# working.net
KiCad netlist of a schematic drawn in EAGLE
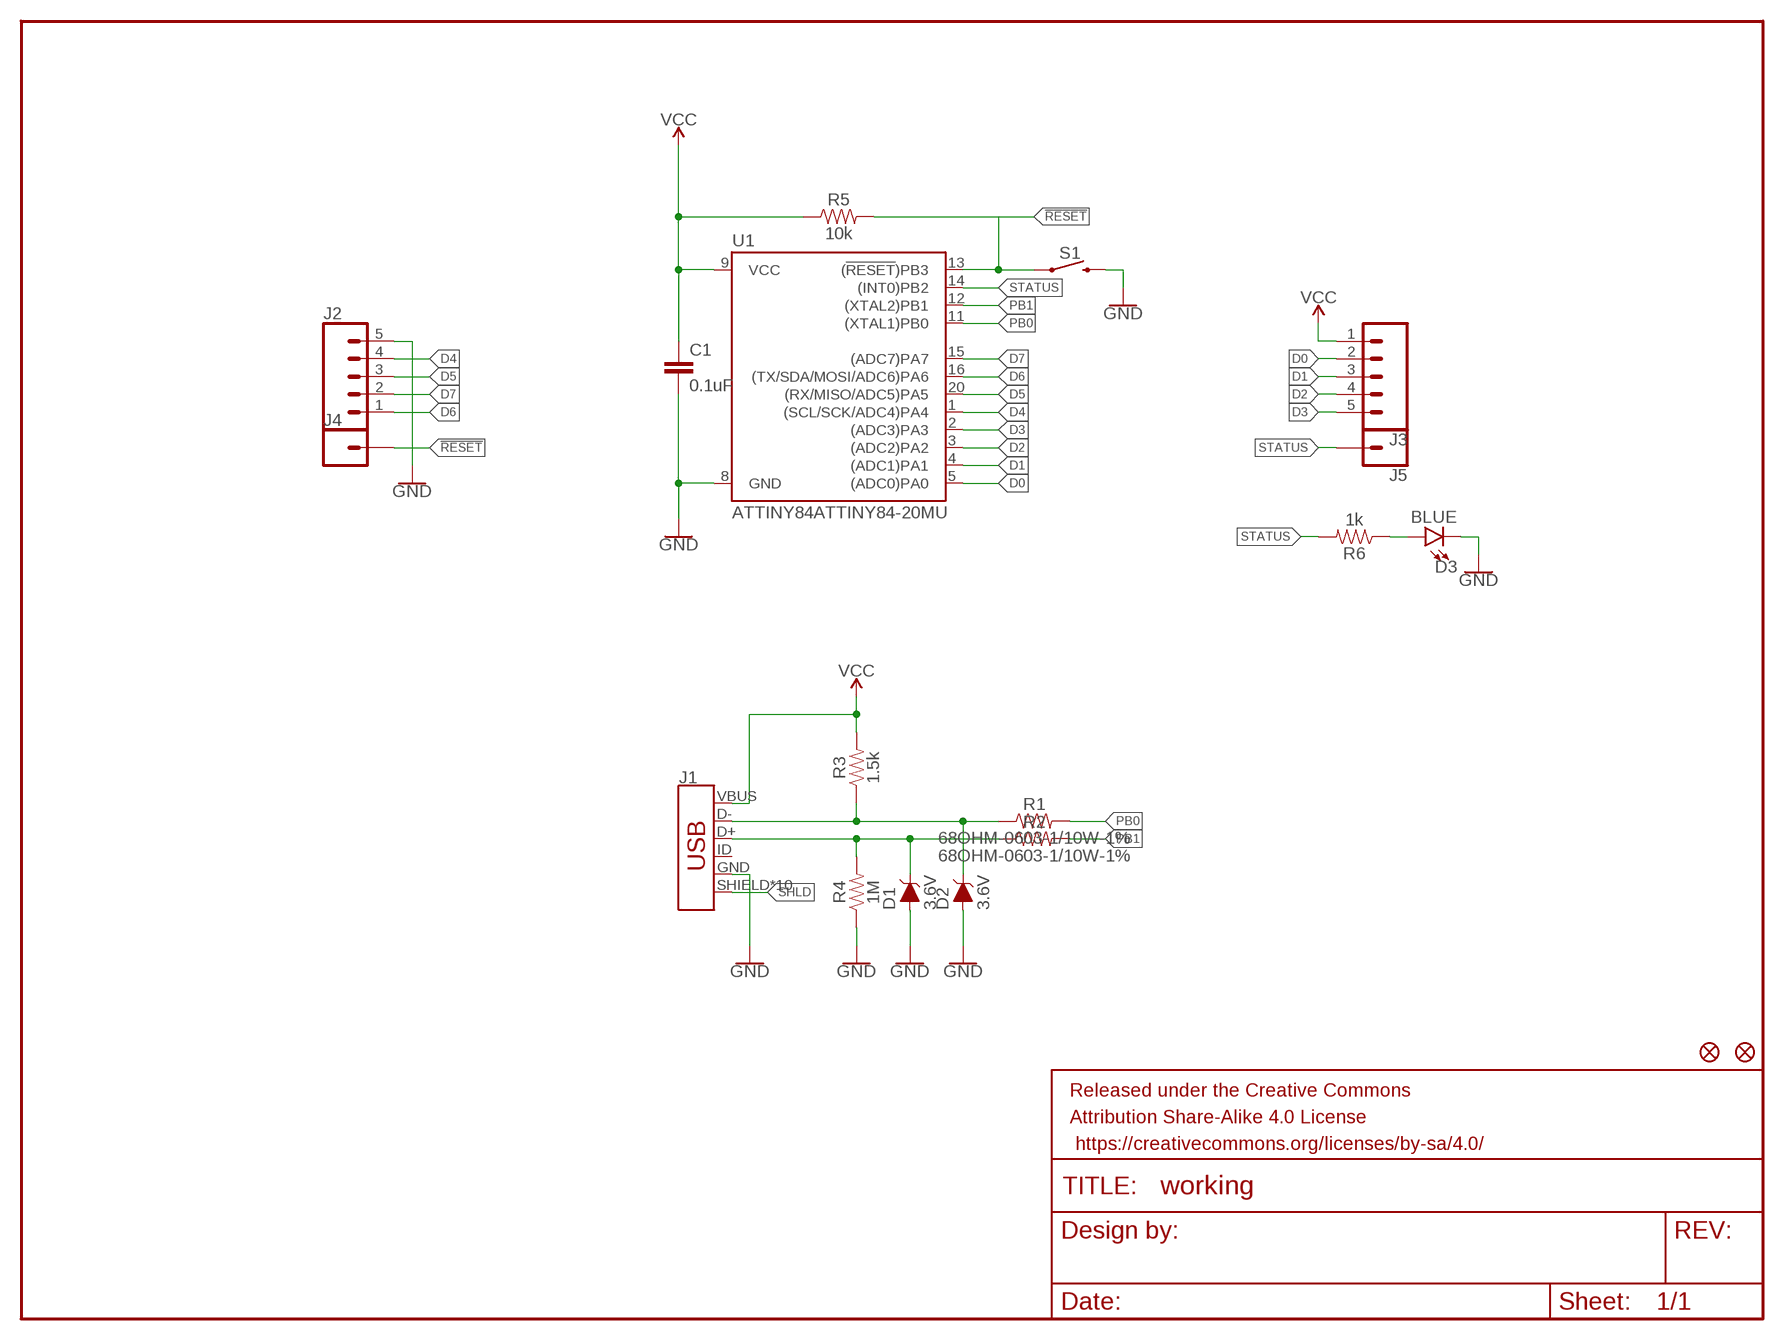
[diagram p0: schematic, sheet 1]

(export (version "E")
  (design (tool "Eeschema 10.0.6"))
  (components
    (comp (ref "C1")
      (value "0.1uF")
      (footprint "eagle-import:0603")
      (libsource (lib "eagle-import") (part "0.1UF-0603-25V-(+80/-20%)"))
    )
    (comp (ref "D1")
      (value "3.6V")
      (footprint "eagle-import:SOD-323")
      (libsource (lib "eagle-import") (part "DIODE-ZENER-BZT52C3V6S"))
    )
    (comp (ref "D2")
      (value "3.6V")
      (footprint "eagle-import:SOD-323")
      (libsource (lib "eagle-import") (part "DIODE-ZENER-BZT52C3V6S"))
    )
    (comp (ref "D3")
      (value "BLUE")
      (footprint "eagle-import:LED-0603")
      (libsource (lib "eagle-import") (part "LED-BLUE0603"))
    )
    (comp (ref "FD1")
      (value "FIDUCIALUFIDUCIAL")
      (footprint "eagle-import:FIDUCIAL-MICRO")
      (libsource (lib "eagle-import") (part "FIDUCIALUFIDUCIAL"))
    )
    (comp (ref "FD2")
      (value "FIDUCIALUFIDUCIAL")
      (footprint "eagle-import:FIDUCIAL-MICRO")
      (libsource (lib "eagle-import") (part "FIDUCIALUFIDUCIAL"))
    )
    (comp (ref "FRAME1")
      (value "FRAME-LETTER")
      (footprint "eagle-import:CREATIVE_COMMONS")
      (libsource (lib "eagle-import") (part "FRAME-LETTER"))
    )
    (comp (ref "J1")
      (value "USB_MICRO-B_HALF_PTH_MILL")
      (footprint "eagle-import:USB-MICROB-PTH-MILL")
      (libsource (lib "eagle-import") (part "USB_MICRO-B_HALF_PTH_MILL"))
    )
    (comp (ref "J2")
      (value "CONN_05NO_SILK")
      (footprint "eagle-import:1X05_NO_SILK")
      (libsource (lib "eagle-import") (part "CONN_05NO_SILK"))
    )
    (comp (ref "J3")
      (value "CONN_05NO_SILK")
      (footprint "eagle-import:1X05_NO_SILK")
      (libsource (lib "eagle-import") (part "CONN_05NO_SILK"))
    )
    (comp (ref "J4")
      (value "CONN_01PTH_NO_SILK_YES_STOP")
      (footprint "eagle-import:1X01_NO_SILK")
      (libsource (lib "eagle-import") (part "CONN_01PTH_NO_SILK_YES_STOP"))
    )
    (comp (ref "J5")
      (value "CONN_01PTH_NO_SILK_YES_STOP")
      (footprint "eagle-import:1X01_NO_SILK")
      (libsource (lib "eagle-import") (part "CONN_01PTH_NO_SILK_YES_STOP"))
    )
    (comp (ref "R1")
      (value "68OHM-0603-1/10W-1%")
      (footprint "eagle-import:0603")
      (libsource (lib "eagle-import") (part "68OHM-0603-1/10W-1%"))
    )
    (comp (ref "R2")
      (value "68OHM-0603-1/10W-1%")
      (footprint "eagle-import:0603")
      (libsource (lib "eagle-import") (part "68OHM-0603-1/10W-1%"))
    )
    (comp (ref "R3")
      (value "1.5k")
      (footprint "eagle-import:0603")
      (libsource (lib "eagle-import") (part "1.5KOHM-0603-1/10W-1%"))
    )
    (comp (ref "R4")
      (value "1M")
      (footprint "eagle-import:0603")
      (libsource (lib "eagle-import") (part "1MOHM-0603-1/4W-5%"))
    )
    (comp (ref "R5")
      (value "10k")
      (footprint "eagle-import:0603")
      (libsource (lib "eagle-import") (part "10KOHM-0603-1/10W-1%"))
    )
    (comp (ref "R6")
      (value "1k")
      (footprint "eagle-import:0603")
      (libsource (lib "eagle-import") (part "1KOHM-0603-1/10W-1%"))
    )
    (comp (ref "S1")
      (value "MOMENTARY-SWITCH-SPST-SMD-6.0X3.5MM")
      (footprint "eagle-import:TACTILE_SWITCH_SMD_6.0X3.5MM")
      (libsource (lib "eagle-import") (part "MOMENTARY-SWITCH-SPST-SMD-6.0X3.5MM"))
    )
    (comp (ref "U1")
      (value "ATTINY84ATTINY84-20MU")
      (footprint "eagle-import:QFN20")
      (libsource (lib "eagle-import") (part "ATTINY84ATTINY84-20MU"))
    )
  )
  (nets
    (net (code "1") (name "/~{RESET}") (class "Default")
      (node (ref "J4") (pin "1") (pinfunction "1_1") (pintype "passive"))
      (node (ref "R5") (pin "2") (pinfunction "2_2") (pintype "passive"))
      (node (ref "S1") (pin "1") (pinfunction "1_1") (pintype "passive"))
      (node (ref "U1") (pin "13") (pinfunction "(~{RESET})PB3_13") (pintype "bidirectional"))
    )
    (net (code "2") (name "D0") (class "Default")
      (node (ref "J3") (pin "2") (pinfunction "2_2") (pintype "passive"))
      (node (ref "U1") (pin "5") (pinfunction "(ADC0)PA0_5") (pintype "bidirectional"))
    )
    (net (code "3") (name "D1") (class "Default")
      (node (ref "J3") (pin "3") (pinfunction "3_3") (pintype "passive"))
      (node (ref "U1") (pin "4") (pinfunction "(ADC1)PA1_4") (pintype "bidirectional"))
    )
    (net (code "4") (name "D2") (class "Default")
      (node (ref "J3") (pin "4") (pinfunction "4_4") (pintype "passive"))
      (node (ref "U1") (pin "3") (pinfunction "(ADC2)PA2_3") (pintype "bidirectional"))
    )
    (net (code "5") (name "D3") (class "Default")
      (node (ref "J3") (pin "5") (pinfunction "5_5") (pintype "passive"))
      (node (ref "U1") (pin "2") (pinfunction "(ADC3)PA3_2") (pintype "bidirectional"))
    )
    (net (code "6") (name "D4") (class "Default")
      (node (ref "J2") (pin "4") (pinfunction "4_4") (pintype "passive"))
      (node (ref "U1") (pin "1") (pinfunction "(SCL/SCK/ADC4)PA4_1") (pintype "bidirectional"))
    )
    (net (code "7") (name "D5") (class "Default")
      (node (ref "J2") (pin "3") (pinfunction "3_3") (pintype "passive"))
      (node (ref "U1") (pin "20") (pinfunction "(RX/MISO/ADC5)PA5_20") (pintype "bidirectional"))
    )
    (net (code "8") (name "D6") (class "Default")
      (node (ref "J2") (pin "1") (pinfunction "1_1") (pintype "passive"))
      (node (ref "U1") (pin "16") (pinfunction "(TX/SDA/MOSI/ADC6)PA6_16") (pintype "bidirectional"))
    )
    (net (code "9") (name "D7") (class "Default")
      (node (ref "J2") (pin "2") (pinfunction "2_2") (pintype "passive"))
      (node (ref "U1") (pin "15") (pinfunction "(ADC7)PA7_15") (pintype "bidirectional"))
    )
    (net (code "10") (name "GND") (class "Default")
      (node (ref "C1") (pin "2") (pinfunction "2_2") (pintype "passive"))
      (node (ref "D1") (pin "A") (pinfunction "A_A") (pintype "passive"))
      (node (ref "D2") (pin "A") (pinfunction "A_A") (pintype "passive"))
      (node (ref "D3") (pin "C") (pinfunction "C_C") (pintype "passive"))
      (node (ref "J1") (pin "GND") (pinfunction "GND_GND") (pintype "power_in"))
      (node (ref "J2") (pin "5") (pinfunction "5_5") (pintype "passive"))
      (node (ref "R4") (pin "1") (pinfunction "1_1") (pintype "passive"))
      (node (ref "S1") (pin "2") (pinfunction "2_2") (pintype "passive"))
      (node (ref "U1") (pin "8") (pinfunction "GND_8") (pintype "bidirectional"))
    )
    (net (code "11") (name "Net-(D1-PadC)") (class "Default")
      (node (ref "D1") (pin "C") (pinfunction "C_C") (pintype "passive"))
      (node (ref "J1") (pin "D+") (pinfunction "D+_D+") (pintype "bidirectional"))
      (node (ref "R2") (pin "1") (pinfunction "1_1") (pintype "passive"))
      (node (ref "R4") (pin "2") (pinfunction "2_2") (pintype "passive"))
    )
    (net (code "12") (name "Net-(D2-PadC)") (class "Default")
      (node (ref "D2") (pin "C") (pinfunction "C_C") (pintype "passive"))
      (node (ref "J1") (pin "D-") (pinfunction "D-_D-") (pintype "bidirectional"))
      (node (ref "R1") (pin "1") (pinfunction "1_1") (pintype "passive"))
      (node (ref "R3") (pin "1") (pinfunction "1_1") (pintype "passive"))
    )
    (net (code "13") (name "Net-(D3-PadA)") (class "Default")
      (node (ref "D3") (pin "A") (pinfunction "A_A") (pintype "passive"))
      (node (ref "R6") (pin "1") (pinfunction "1_1") (pintype "passive"))
    )
    (net (code "14") (name "PB0") (class "Default")
      (node (ref "R1") (pin "2") (pinfunction "2_2") (pintype "passive"))
      (node (ref "U1") (pin "11") (pinfunction "(XTAL1)PB0_11") (pintype "bidirectional"))
    )
    (net (code "15") (name "PB1") (class "Default")
      (node (ref "R2") (pin "2") (pinfunction "2_2") (pintype "passive"))
      (node (ref "U1") (pin "12") (pinfunction "(XTAL2)PB1_12") (pintype "bidirectional"))
    )
    (net (code "16") (name "SHLD") (class "Default")
      (node (ref "J1") (pin "SHIELD") (pinfunction "SHIELD_SHIELD") (pintype "bidirectional"))
      (node (ref "J1") (pin "SHIELD10") (pinfunction "SHIELD_SHIELD10") (pintype "bidirectional"))
      (node (ref "J1") (pin "SHIELD2") (pinfunction "SHIELD_SHIELD2") (pintype "bidirectional"))
      (node (ref "J1") (pin "SHIELD3") (pinfunction "SHIELD_SHIELD3") (pintype "bidirectional"))
      (node (ref "J1") (pin "SHIELD4") (pinfunction "SHIELD_SHIELD4") (pintype "bidirectional"))
      (node (ref "J1") (pin "SHIELD5") (pinfunction "SHIELD_SHIELD5") (pintype "bidirectional"))
      (node (ref "J1") (pin "SHIELD6") (pinfunction "SHIELD_SHIELD6") (pintype "bidirectional"))
      (node (ref "J1") (pin "SHIELD7") (pinfunction "SHIELD_SHIELD7") (pintype "bidirectional"))
      (node (ref "J1") (pin "SHIELD8") (pinfunction "SHIELD_SHIELD8") (pintype "bidirectional"))
      (node (ref "J1") (pin "SHIELD9") (pinfunction "SHIELD_SHIELD9") (pintype "bidirectional"))
    )
    (net (code "17") (name "STATUS") (class "Default")
      (node (ref "J5") (pin "1") (pinfunction "1_1") (pintype "passive"))
      (node (ref "R6") (pin "2") (pinfunction "2_2") (pintype "passive"))
      (node (ref "U1") (pin "14") (pinfunction "(INT0)PB2_14") (pintype "bidirectional"))
    )
    (net (code "18") (name "VCC") (class "Default")
      (node (ref "C1") (pin "1") (pinfunction "1_1") (pintype "passive"))
      (node (ref "J1") (pin "VBUS") (pinfunction "VBUS_VBUS") (pintype "power_in"))
      (node (ref "J3") (pin "1") (pinfunction "1_1") (pintype "passive"))
      (node (ref "R3") (pin "2") (pinfunction "2_2") (pintype "passive"))
      (node (ref "R5") (pin "1") (pinfunction "1_1") (pintype "passive"))
      (node (ref "U1") (pin "9") (pinfunction "VCC_9") (pintype "bidirectional"))
    )
    (net (code "19") (name "unconnected-(J1-PadID)") (class "Default")
      (node (ref "J1") (pin "ID") (pinfunction "ID_ID") (pintype "bidirectional"))
    )
  )
)
